# EPM240T100C5N_2.net
KiCad netlist of a schematic drawn in Altium Designer
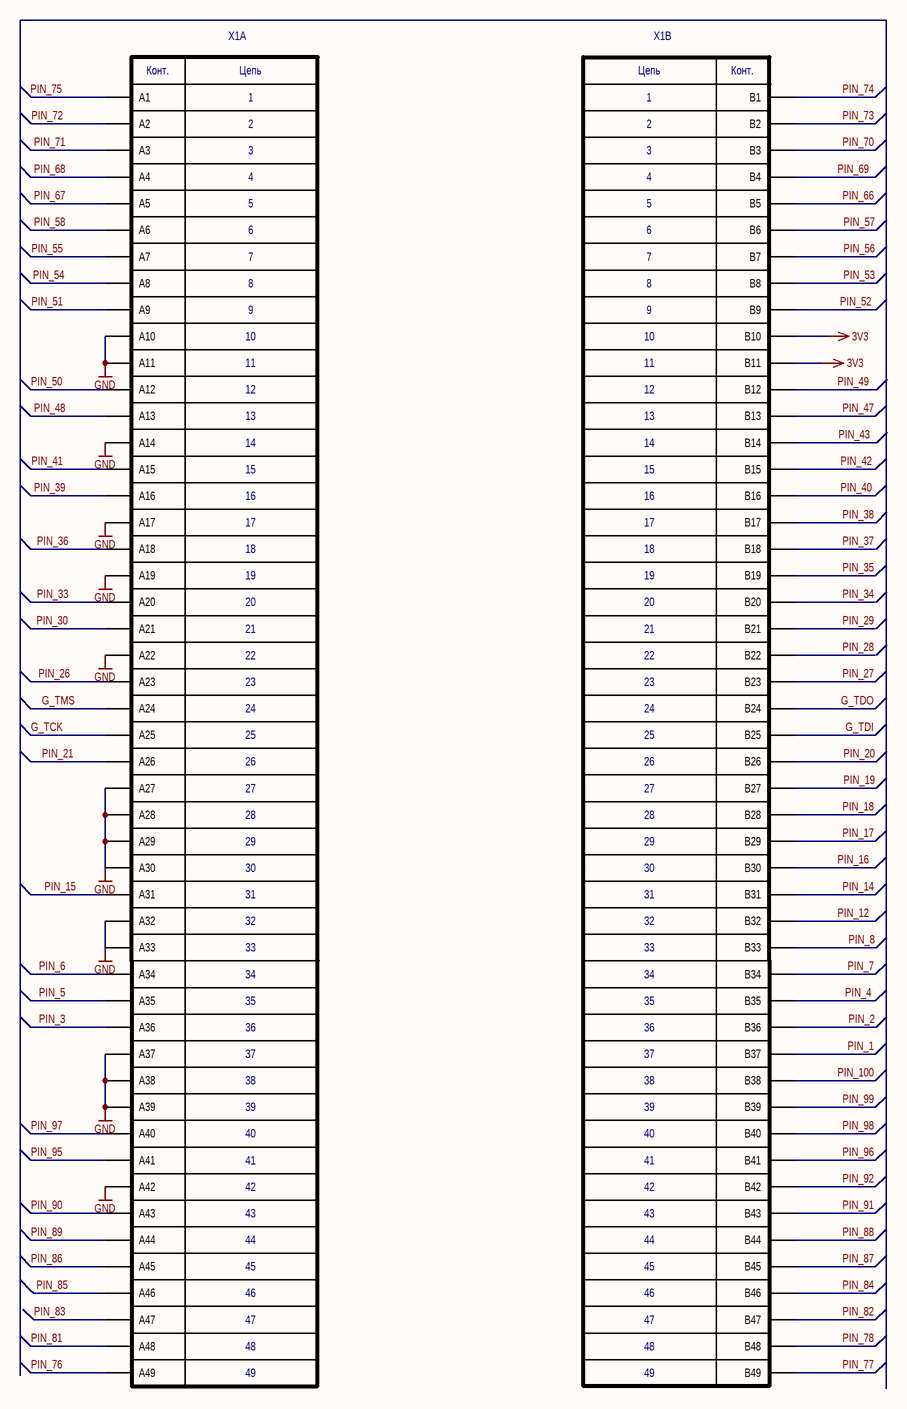
[diagram p0: EPM240T100C5N_2.SchDoc]

(export (version "E")
  (design (tool "Eeschema 10.0.6"))
  (components
    (comp (ref "X1")
      (value "KONT_POLE_MEZ")
      (footprint "3113-112t_otv")
      (libsource (lib "Lisaveta_SCH") (part "3113-112T"))
    )
  )
  (nets
    (net (code "1") (name "/G_TCK") (class "Default")
      (node (ref "X1") (pin "A25") (pinfunction "A25_A25") (pintype "passive"))
    )
    (net (code "2") (name "/G_TDI") (class "Default")
      (node (ref "X1") (pin "B25") (pinfunction "B25_B25") (pintype "passive"))
    )
    (net (code "3") (name "/G_TDO") (class "Default")
      (node (ref "X1") (pin "B24") (pinfunction "B24_B24") (pintype "passive"))
    )
    (net (code "4") (name "/G_TMS") (class "Default")
      (node (ref "X1") (pin "A24") (pinfunction "A24_A24") (pintype "passive"))
    )
    (net (code "5") (name "/PIN_1") (class "Default")
      (node (ref "X1") (pin "B37") (pinfunction "B37_B37") (pintype "passive"))
    )
    (net (code "6") (name "/PIN_2") (class "Default")
      (node (ref "X1") (pin "B36") (pinfunction "B36_B36") (pintype "passive"))
    )
    (net (code "7") (name "/PIN_3") (class "Default")
      (node (ref "X1") (pin "A36") (pinfunction "A36_A36") (pintype "passive"))
    )
    (net (code "8") (name "/PIN_4") (class "Default")
      (node (ref "X1") (pin "B35") (pinfunction "B35_B35") (pintype "passive"))
    )
    (net (code "9") (name "/PIN_5") (class "Default")
      (node (ref "X1") (pin "A35") (pinfunction "A35_A35") (pintype "passive"))
    )
    (net (code "10") (name "/PIN_6") (class "Default")
      (node (ref "X1") (pin "A34") (pinfunction "A34_A34") (pintype "passive"))
    )
    (net (code "11") (name "/PIN_7") (class "Default")
      (node (ref "X1") (pin "B34") (pinfunction "B34_B34") (pintype "passive"))
    )
    (net (code "12") (name "/PIN_8") (class "Default")
      (node (ref "X1") (pin "B33") (pinfunction "B33_B33") (pintype "passive"))
    )
    (net (code "13") (name "/PIN_12") (class "Default")
      (node (ref "X1") (pin "B32") (pinfunction "B32_B32") (pintype "passive"))
    )
    (net (code "14") (name "/PIN_14") (class "Default")
      (node (ref "X1") (pin "B31") (pinfunction "B31_B31") (pintype "passive"))
    )
    (net (code "15") (name "/PIN_15") (class "Default")
      (node (ref "X1") (pin "A31") (pinfunction "A31_A31") (pintype "passive"))
    )
    (net (code "16") (name "/PIN_16") (class "Default")
      (node (ref "X1") (pin "B30") (pinfunction "B30_B30") (pintype "passive"))
    )
    (net (code "17") (name "/PIN_17") (class "Default")
      (node (ref "X1") (pin "B29") (pinfunction "B29_B29") (pintype "passive"))
    )
    (net (code "18") (name "/PIN_18") (class "Default")
      (node (ref "X1") (pin "B28") (pinfunction "B28_B28") (pintype "passive"))
    )
    (net (code "19") (name "/PIN_19") (class "Default")
      (node (ref "X1") (pin "B27") (pinfunction "B27_B27") (pintype "passive"))
    )
    (net (code "20") (name "/PIN_20") (class "Default")
      (node (ref "X1") (pin "B26") (pinfunction "B26_B26") (pintype "passive"))
    )
    (net (code "21") (name "/PIN_21") (class "Default")
      (node (ref "X1") (pin "A26") (pinfunction "A26_A26") (pintype "passive"))
    )
    (net (code "22") (name "/PIN_26") (class "Default")
      (node (ref "X1") (pin "A23") (pinfunction "A23_A23") (pintype "passive"))
    )
    (net (code "23") (name "/PIN_27") (class "Default")
      (node (ref "X1") (pin "B23") (pinfunction "B23_B23") (pintype "passive"))
    )
    (net (code "24") (name "/PIN_28") (class "Default")
      (node (ref "X1") (pin "B22") (pinfunction "B22_B22") (pintype "passive"))
    )
    (net (code "25") (name "/PIN_29") (class "Default")
      (node (ref "X1") (pin "B21") (pinfunction "B21_B21") (pintype "passive"))
    )
    (net (code "26") (name "/PIN_30") (class "Default")
      (node (ref "X1") (pin "A21") (pinfunction "A21_A21") (pintype "passive"))
    )
    (net (code "27") (name "/PIN_33") (class "Default")
      (node (ref "X1") (pin "A20") (pinfunction "A20_A20") (pintype "passive"))
    )
    (net (code "28") (name "/PIN_34") (class "Default")
      (node (ref "X1") (pin "B20") (pinfunction "B20_B20") (pintype "passive"))
    )
    (net (code "29") (name "/PIN_35") (class "Default")
      (node (ref "X1") (pin "B19") (pinfunction "B19_B19") (pintype "passive"))
    )
    (net (code "30") (name "/PIN_36") (class "Default")
      (node (ref "X1") (pin "A18") (pinfunction "A18_A18") (pintype "passive"))
    )
    (net (code "31") (name "/PIN_37") (class "Default")
      (node (ref "X1") (pin "B18") (pinfunction "B18_B18") (pintype "passive"))
    )
    (net (code "32") (name "/PIN_38") (class "Default")
      (node (ref "X1") (pin "B17") (pinfunction "B17_B17") (pintype "passive"))
    )
    (net (code "33") (name "/PIN_39") (class "Default")
      (node (ref "X1") (pin "A16") (pinfunction "A16_A16") (pintype "passive"))
    )
    (net (code "34") (name "/PIN_40") (class "Default")
      (node (ref "X1") (pin "B16") (pinfunction "B16_B16") (pintype "passive"))
    )
    (net (code "35") (name "/PIN_41") (class "Default")
      (node (ref "X1") (pin "A15") (pinfunction "A15_A15") (pintype "passive"))
    )
    (net (code "36") (name "/PIN_42") (class "Default")
      (node (ref "X1") (pin "B15") (pinfunction "B15_B15") (pintype "passive"))
    )
    (net (code "37") (name "/PIN_43") (class "Default")
      (node (ref "X1") (pin "B14") (pinfunction "B14_B14") (pintype "passive"))
    )
    (net (code "38") (name "/PIN_47") (class "Default")
      (node (ref "X1") (pin "B13") (pinfunction "B13_B13") (pintype "passive"))
    )
    (net (code "39") (name "/PIN_48") (class "Default")
      (node (ref "X1") (pin "A13") (pinfunction "A13_A13") (pintype "passive"))
    )
    (net (code "40") (name "/PIN_49") (class "Default")
      (node (ref "X1") (pin "B12") (pinfunction "B12_B12") (pintype "passive"))
    )
    (net (code "41") (name "/PIN_50") (class "Default")
      (node (ref "X1") (pin "A12") (pinfunction "A12_A12") (pintype "passive"))
    )
    (net (code "42") (name "/PIN_51") (class "Default")
      (node (ref "X1") (pin "A9") (pinfunction "A9_A9") (pintype "passive"))
    )
    (net (code "43") (name "/PIN_52") (class "Default")
      (node (ref "X1") (pin "B9") (pinfunction "B9_B9") (pintype "passive"))
    )
    (net (code "44") (name "/PIN_53") (class "Default")
      (node (ref "X1") (pin "B8") (pinfunction "B8_B8") (pintype "passive"))
    )
    (net (code "45") (name "/PIN_54") (class "Default")
      (node (ref "X1") (pin "A8") (pinfunction "A8_A8") (pintype "passive"))
    )
    (net (code "46") (name "/PIN_55") (class "Default")
      (node (ref "X1") (pin "A7") (pinfunction "A7_A7") (pintype "passive"))
    )
    (net (code "47") (name "/PIN_56") (class "Default")
      (node (ref "X1") (pin "B7") (pinfunction "B7_B7") (pintype "passive"))
    )
    (net (code "48") (name "/PIN_57") (class "Default")
      (node (ref "X1") (pin "B6") (pinfunction "B6_B6") (pintype "passive"))
    )
    (net (code "49") (name "/PIN_58") (class "Default")
      (node (ref "X1") (pin "A6") (pinfunction "A6_A6") (pintype "passive"))
    )
    (net (code "50") (name "/PIN_66") (class "Default")
      (node (ref "X1") (pin "B5") (pinfunction "B5_B5") (pintype "passive"))
    )
    (net (code "51") (name "/PIN_67") (class "Default")
      (node (ref "X1") (pin "A5") (pinfunction "A5_A5") (pintype "passive"))
    )
    (net (code "52") (name "/PIN_68") (class "Default")
      (node (ref "X1") (pin "A4") (pinfunction "A4_A4") (pintype "passive"))
    )
    (net (code "53") (name "/PIN_69") (class "Default")
      (node (ref "X1") (pin "B4") (pinfunction "B4_B4") (pintype "passive"))
    )
    (net (code "54") (name "/PIN_70") (class "Default")
      (node (ref "X1") (pin "B3") (pinfunction "B3_B3") (pintype "passive"))
    )
    (net (code "55") (name "/PIN_71") (class "Default")
      (node (ref "X1") (pin "A3") (pinfunction "A3_A3") (pintype "passive"))
    )
    (net (code "56") (name "/PIN_72") (class "Default")
      (node (ref "X1") (pin "A2") (pinfunction "A2_A2") (pintype "passive"))
    )
    (net (code "57") (name "/PIN_73") (class "Default")
      (node (ref "X1") (pin "B2") (pinfunction "B2_B2") (pintype "passive"))
    )
    (net (code "58") (name "/PIN_74") (class "Default")
      (node (ref "X1") (pin "B1") (pinfunction "B1_B1") (pintype "passive"))
    )
    (net (code "59") (name "/PIN_75") (class "Default")
      (node (ref "X1") (pin "A1") (pinfunction "A1_A1") (pintype "passive"))
    )
    (net (code "60") (name "/PIN_76") (class "Default")
      (node (ref "X1") (pin "A49") (pinfunction "A49_A49") (pintype "passive"))
    )
    (net (code "61") (name "/PIN_77") (class "Default")
      (node (ref "X1") (pin "B49") (pinfunction "B49_B49") (pintype "passive"))
    )
    (net (code "62") (name "/PIN_78") (class "Default")
      (node (ref "X1") (pin "B48") (pinfunction "B48_B48") (pintype "passive"))
    )
    (net (code "63") (name "/PIN_81") (class "Default")
      (node (ref "X1") (pin "A48") (pinfunction "A48_A48") (pintype "passive"))
    )
    (net (code "64") (name "/PIN_82") (class "Default")
      (node (ref "X1") (pin "B47") (pinfunction "B47_B47") (pintype "passive"))
    )
    (net (code "65") (name "/PIN_83") (class "Default")
      (node (ref "X1") (pin "A47") (pinfunction "A47_A47") (pintype "passive"))
    )
    (net (code "66") (name "/PIN_84") (class "Default")
      (node (ref "X1") (pin "B46") (pinfunction "B46_B46") (pintype "passive"))
    )
    (net (code "67") (name "/PIN_85") (class "Default")
      (node (ref "X1") (pin "A46") (pinfunction "A46_A46") (pintype "passive"))
    )
    (net (code "68") (name "/PIN_86") (class "Default")
      (node (ref "X1") (pin "A45") (pinfunction "A45_A45") (pintype "passive"))
    )
    (net (code "69") (name "/PIN_87") (class "Default")
      (node (ref "X1") (pin "B45") (pinfunction "B45_B45") (pintype "passive"))
    )
    (net (code "70") (name "/PIN_88") (class "Default")
      (node (ref "X1") (pin "B44") (pinfunction "B44_B44") (pintype "passive"))
    )
    (net (code "71") (name "/PIN_89") (class "Default")
      (node (ref "X1") (pin "A44") (pinfunction "A44_A44") (pintype "passive"))
    )
    (net (code "72") (name "/PIN_90") (class "Default")
      (node (ref "X1") (pin "A43") (pinfunction "A43_A43") (pintype "passive"))
    )
    (net (code "73") (name "/PIN_91") (class "Default")
      (node (ref "X1") (pin "B43") (pinfunction "B43_B43") (pintype "passive"))
    )
    (net (code "74") (name "/PIN_92") (class "Default")
      (node (ref "X1") (pin "B42") (pinfunction "B42_B42") (pintype "passive"))
    )
    (net (code "75") (name "/PIN_95") (class "Default")
      (node (ref "X1") (pin "A41") (pinfunction "A41_A41") (pintype "passive"))
    )
    (net (code "76") (name "/PIN_96") (class "Default")
      (node (ref "X1") (pin "B41") (pinfunction "B41_B41") (pintype "passive"))
    )
    (net (code "77") (name "/PIN_97") (class "Default")
      (node (ref "X1") (pin "A40") (pinfunction "A40_A40") (pintype "passive"))
    )
    (net (code "78") (name "/PIN_98") (class "Default")
      (node (ref "X1") (pin "B40") (pinfunction "B40_B40") (pintype "passive"))
    )
    (net (code "79") (name "/PIN_99") (class "Default")
      (node (ref "X1") (pin "B39") (pinfunction "B39_B39") (pintype "passive"))
    )
    (net (code "80") (name "/PIN_100") (class "Default")
      (node (ref "X1") (pin "B38") (pinfunction "B38_B38") (pintype "passive"))
    )
    (net (code "81") (name "3V3") (class "Default")
      (node (ref "X1") (pin "B10") (pinfunction "B10_B10") (pintype "passive"))
      (node (ref "X1") (pin "B11") (pinfunction "B11_B11") (pintype "passive"))
    )
    (net (code "82") (name "GND") (class "Default")
      (node (ref "X1") (pin "A10") (pinfunction "A10_A10") (pintype "passive"))
      (node (ref "X1") (pin "A11") (pinfunction "A11_A11") (pintype "passive"))
      (node (ref "X1") (pin "A14") (pinfunction "A14_A14") (pintype "passive"))
      (node (ref "X1") (pin "A17") (pinfunction "A17_A17") (pintype "passive"))
      (node (ref "X1") (pin "A19") (pinfunction "A19_A19") (pintype "passive"))
      (node (ref "X1") (pin "A22") (pinfunction "A22_A22") (pintype "passive"))
      (node (ref "X1") (pin "A27") (pinfunction "A27_A27") (pintype "passive"))
      (node (ref "X1") (pin "A28") (pinfunction "A28_A28") (pintype "passive"))
      (node (ref "X1") (pin "A29") (pinfunction "A29_A29") (pintype "passive"))
      (node (ref "X1") (pin "A30") (pinfunction "A30_A30") (pintype "passive"))
      (node (ref "X1") (pin "A32") (pinfunction "A32_A32") (pintype "passive"))
      (node (ref "X1") (pin "A33") (pinfunction "A33_A33") (pintype "passive"))
      (node (ref "X1") (pin "A37") (pinfunction "A37_A37") (pintype "passive"))
      (node (ref "X1") (pin "A38") (pinfunction "A38_A38") (pintype "passive"))
      (node (ref "X1") (pin "A39") (pinfunction "A39_A39") (pintype "passive"))
      (node (ref "X1") (pin "A42") (pinfunction "A42_A42") (pintype "passive"))
    )
  )
)
